# board.net
KiCad netlist of a schematic drawn in EAGLE
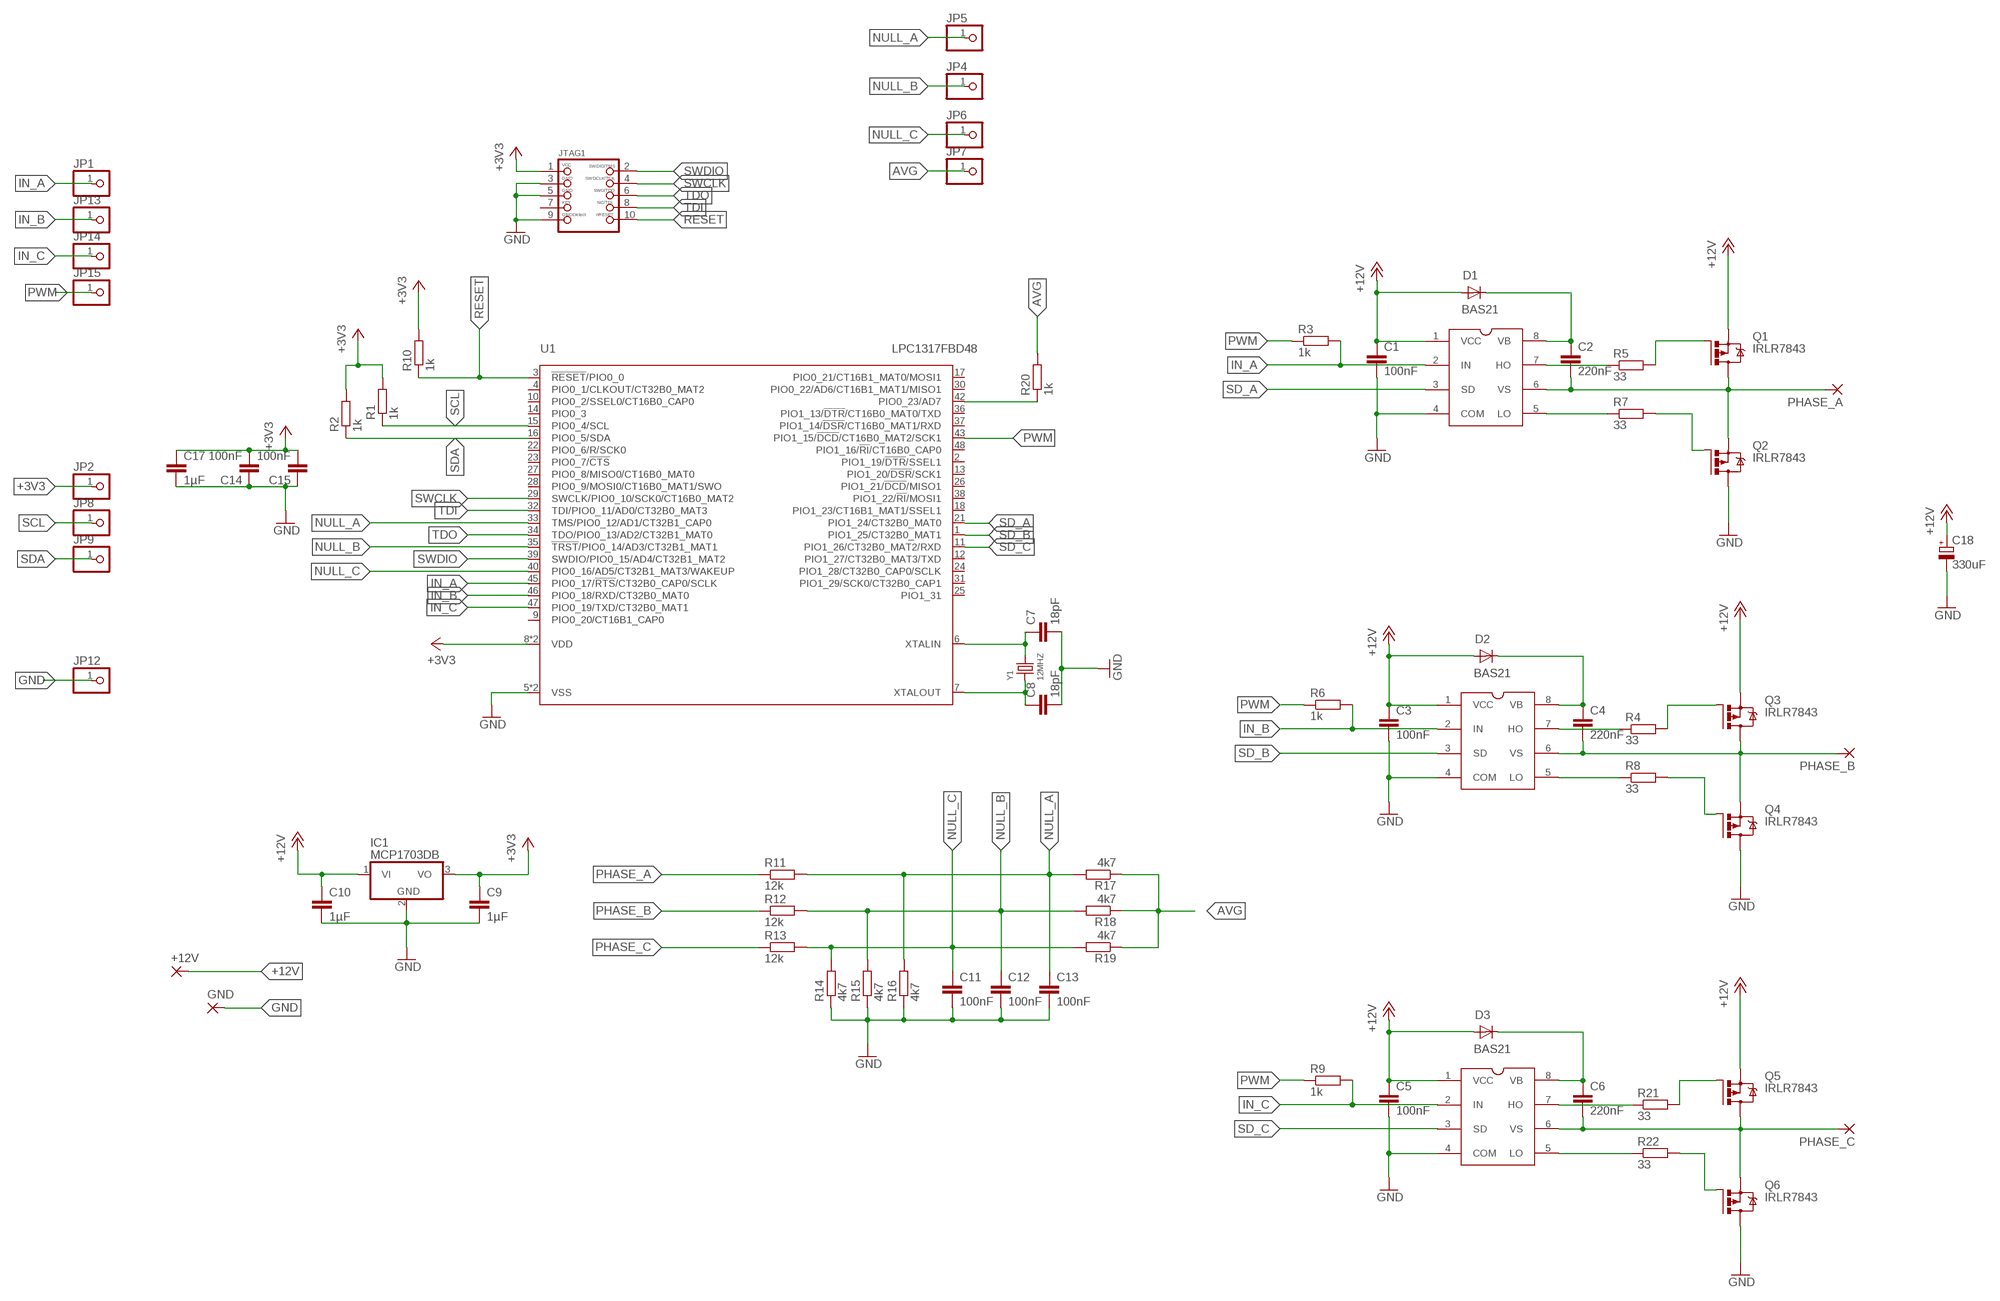
[diagram p0: schematic, sheet 1]

(export (version "E")
  (design (tool "Eeschema 10.0.6"))
  (components
    (comp (ref "+12V")
      (value "SMD5")
      (footprint "eagle-import:SMD2,54-5,08")
      (libsource (lib "eagle-import") (part "SMD5"))
    )
    (comp (ref "C1")
      (value "100nF")
      (footprint "eagle-import:C0603")
      (libsource (lib "eagle-import") (part "C-EUC0603"))
    )
    (comp (ref "C2")
      (value "220nF")
      (footprint "eagle-import:C0603")
      (libsource (lib "eagle-import") (part "C-EUC0603"))
    )
    (comp (ref "C3")
      (value "100nF")
      (footprint "eagle-import:C0603")
      (libsource (lib "eagle-import") (part "C-EUC0603"))
    )
    (comp (ref "C4")
      (value "220nF")
      (footprint "eagle-import:C0603")
      (libsource (lib "eagle-import") (part "C-EUC0603"))
    )
    (comp (ref "C5")
      (value "100nF")
      (footprint "eagle-import:C0603")
      (libsource (lib "eagle-import") (part "C-EUC0603"))
    )
    (comp (ref "C6")
      (value "220nF")
      (footprint "eagle-import:C0603")
      (libsource (lib "eagle-import") (part "C-EUC0603"))
    )
    (comp (ref "C7")
      (value "18pF")
      (footprint "eagle-import:C0603")
      (libsource (lib "eagle-import") (part "C-EUC0603"))
    )
    (comp (ref "C8")
      (value "18pF")
      (footprint "eagle-import:C0603")
      (libsource (lib "eagle-import") (part "C-EUC0603"))
    )
    (comp (ref "C9")
      (value "1µF")
      (footprint "eagle-import:C0603")
      (libsource (lib "eagle-import") (part "C-EUC0603"))
    )
    (comp (ref "C10")
      (value "1µF")
      (footprint "eagle-import:C0603")
      (libsource (lib "eagle-import") (part "C-EUC0603"))
    )
    (comp (ref "C11")
      (value "100nF")
      (footprint "eagle-import:C0603")
      (libsource (lib "eagle-import") (part "C-EUC0603"))
    )
    (comp (ref "C12")
      (value "100nF")
      (footprint "eagle-import:C0603")
      (libsource (lib "eagle-import") (part "C-EUC0603"))
    )
    (comp (ref "C13")
      (value "100nF")
      (footprint "eagle-import:C0603")
      (libsource (lib "eagle-import") (part "C-EUC0603"))
    )
    (comp (ref "C14")
      (value "100nF")
      (footprint "eagle-import:C0603")
      (libsource (lib "eagle-import") (part "C-EUC0603"))
    )
    (comp (ref "C15")
      (value "100nF")
      (footprint "eagle-import:C0603")
      (libsource (lib "eagle-import") (part "C-EUC0603"))
    )
    (comp (ref "C17")
      (value "1µF")
      (footprint "eagle-import:C0603")
      (libsource (lib "eagle-import") (part "C-EUC0603"))
    )
    (comp (ref "C18")
      (value "330uF")
      (footprint "eagle-import:E5-10,5")
      (libsource (lib "eagle-import") (part "CPOL-EUE5-10.5"))
    )
    (comp (ref "D1")
      (value "BAS21")
      (footprint "eagle-import:SOT23")
      (libsource (lib "eagle-import") (part "BAS21"))
    )
    (comp (ref "D2")
      (value "BAS21")
      (footprint "eagle-import:SOT23")
      (libsource (lib "eagle-import") (part "BAS21"))
    )
    (comp (ref "D3")
      (value "BAS21")
      (footprint "eagle-import:SOT23")
      (libsource (lib "eagle-import") (part "BAS21"))
    )
    (comp (ref "GND")
      (value "SMD5")
      (footprint "eagle-import:SMD2,54-5,08")
      (libsource (lib "eagle-import") (part "SMD5"))
    )
    (comp (ref "IC1")
      (value "MCP1703DB")
      (footprint "eagle-import:SOT223")
      (libsource (lib "eagle-import") (part "MCP1703DB"))
    )
    (comp (ref "JP1")
      (value "PINHD-1X1")
      (footprint "eagle-import:1X01")
      (libsource (lib "eagle-import") (part "PINHD-1X1"))
    )
    (comp (ref "JP2")
      (value "PINHD-1X1")
      (footprint "eagle-import:1X01")
      (libsource (lib "eagle-import") (part "PINHD-1X1"))
    )
    (comp (ref "JP4")
      (value "PINHD-1X1")
      (footprint "eagle-import:1X01")
      (libsource (lib "eagle-import") (part "PINHD-1X1"))
    )
    (comp (ref "JP5")
      (value "PINHD-1X1")
      (footprint "eagle-import:1X01")
      (libsource (lib "eagle-import") (part "PINHD-1X1"))
    )
    (comp (ref "JP6")
      (value "PINHD-1X1")
      (footprint "eagle-import:1X01")
      (libsource (lib "eagle-import") (part "PINHD-1X1"))
    )
    (comp (ref "JP7")
      (value "PINHD-1X1")
      (footprint "eagle-import:1X01")
      (libsource (lib "eagle-import") (part "PINHD-1X1"))
    )
    (comp (ref "JP8")
      (value "PINHD-1X1")
      (footprint "eagle-import:1X01")
      (libsource (lib "eagle-import") (part "PINHD-1X1"))
    )
    (comp (ref "JP9")
      (value "PINHD-1X1")
      (footprint "eagle-import:1X01")
      (libsource (lib "eagle-import") (part "PINHD-1X1"))
    )
    (comp (ref "JP12")
      (value "PINHD-1X1")
      (footprint "eagle-import:1X01")
      (libsource (lib "eagle-import") (part "PINHD-1X1"))
    )
    (comp (ref "JP13")
      (value "PINHD-1X1")
      (footprint "eagle-import:1X01")
      (libsource (lib "eagle-import") (part "PINHD-1X1"))
    )
    (comp (ref "JP14")
      (value "PINHD-1X1")
      (footprint "eagle-import:1X01")
      (libsource (lib "eagle-import") (part "PINHD-1X1"))
    )
    (comp (ref "JP15")
      (value "PINHD-1X1")
      (footprint "eagle-import:1X01")
      (libsource (lib "eagle-import") (part "PINHD-1X1"))
    )
    (comp (ref "JTAG1")
      (value "JTAG-CORTEXM3")
      (footprint "eagle-import:2X05_1.27MM_SMT")
      (libsource (lib "eagle-import") (part "JTAG-CORTEXM3"))
    )
    (comp (ref "PHASE_A")
      (value "SMD5")
      (footprint "eagle-import:SMD2,54-5,08")
      (libsource (lib "eagle-import") (part "SMD5"))
    )
    (comp (ref "PHASE_B")
      (value "SMD5")
      (footprint "eagle-import:SMD2,54-5,08")
      (libsource (lib "eagle-import") (part "SMD5"))
    )
    (comp (ref "PHASE_C")
      (value "SMD5")
      (footprint "eagle-import:SMD2,54-5,08")
      (libsource (lib "eagle-import") (part "SMD5"))
    )
    (comp (ref "Q1")
      (value "IRLR7843")
      (footprint "eagle-import:D-PAK_TO252AA")
      (libsource (lib "eagle-import") (part "IRF?5305R"))
    )
    (comp (ref "Q2")
      (value "IRLR7843")
      (footprint "eagle-import:D-PAK_TO252AA")
      (libsource (lib "eagle-import") (part "IRF?5305R"))
    )
    (comp (ref "Q3")
      (value "IRLR7843")
      (footprint "eagle-import:D-PAK_TO252AA")
      (libsource (lib "eagle-import") (part "IRF?5305R"))
    )
    (comp (ref "Q4")
      (value "IRLR7843")
      (footprint "eagle-import:D-PAK_TO252AA")
      (libsource (lib "eagle-import") (part "IRF?5305R"))
    )
    (comp (ref "Q5")
      (value "IRLR7843")
      (footprint "eagle-import:D-PAK_TO252AA")
      (libsource (lib "eagle-import") (part "IRF?5305R"))
    )
    (comp (ref "Q6")
      (value "IRLR7843")
      (footprint "eagle-import:D-PAK_TO252AA")
      (libsource (lib "eagle-import") (part "IRF?5305R"))
    )
    (comp (ref "R1")
      (value "1k")
      (footprint "eagle-import:R0603")
      (libsource (lib "eagle-import") (part "R-EU_R0603"))
    )
    (comp (ref "R2")
      (value "1k")
      (footprint "eagle-import:R0603")
      (libsource (lib "eagle-import") (part "R-EU_R0603"))
    )
    (comp (ref "R3")
      (value "1k")
      (footprint "eagle-import:R0603")
      (libsource (lib "eagle-import") (part "R-EU_R0603"))
    )
    (comp (ref "R4")
      (value "33")
      (footprint "eagle-import:R0603")
      (libsource (lib "eagle-import") (part "R-EU_R0603"))
    )
    (comp (ref "R5")
      (value "33")
      (footprint "eagle-import:R0603")
      (libsource (lib "eagle-import") (part "R-EU_R0603"))
    )
    (comp (ref "R6")
      (value "1k")
      (footprint "eagle-import:R0603")
      (libsource (lib "eagle-import") (part "R-EU_R0603"))
    )
    (comp (ref "R7")
      (value "33")
      (footprint "eagle-import:R0603")
      (libsource (lib "eagle-import") (part "R-EU_R0603"))
    )
    (comp (ref "R8")
      (value "33")
      (footprint "eagle-import:R0603")
      (libsource (lib "eagle-import") (part "R-EU_R0603"))
    )
    (comp (ref "R9")
      (value "1k")
      (footprint "eagle-import:R0603")
      (libsource (lib "eagle-import") (part "R-EU_R0603"))
    )
    (comp (ref "R10")
      (value "1k")
      (footprint "eagle-import:R0603")
      (libsource (lib "eagle-import") (part "R-EU_R0603"))
    )
    (comp (ref "R11")
      (value "12k")
      (footprint "eagle-import:R0603")
      (libsource (lib "eagle-import") (part "R-EU_R0603"))
    )
    (comp (ref "R12")
      (value "12k")
      (footprint "eagle-import:R0603")
      (libsource (lib "eagle-import") (part "R-EU_R0603"))
    )
    (comp (ref "R13")
      (value "12k")
      (footprint "eagle-import:R0603")
      (libsource (lib "eagle-import") (part "R-EU_R0603"))
    )
    (comp (ref "R14")
      (value "4k7")
      (footprint "eagle-import:R0603")
      (libsource (lib "eagle-import") (part "R-EU_R0603"))
    )
    (comp (ref "R15")
      (value "4k7")
      (footprint "eagle-import:R0603")
      (libsource (lib "eagle-import") (part "R-EU_R0603"))
    )
    (comp (ref "R16")
      (value "4k7")
      (footprint "eagle-import:R0603")
      (libsource (lib "eagle-import") (part "R-EU_R0603"))
    )
    (comp (ref "R17")
      (value "4k7")
      (footprint "eagle-import:R0603")
      (libsource (lib "eagle-import") (part "R-EU_R0603"))
    )
    (comp (ref "R18")
      (value "4k7")
      (footprint "eagle-import:R0603")
      (libsource (lib "eagle-import") (part "R-EU_R0603"))
    )
    (comp (ref "R19")
      (value "4k7")
      (footprint "eagle-import:R0603")
      (libsource (lib "eagle-import") (part "R-EU_R0603"))
    )
    (comp (ref "R20")
      (value "1k")
      (footprint "eagle-import:R0603")
      (libsource (lib "eagle-import") (part "R-EU_R0603"))
    )
    (comp (ref "R21")
      (value "33")
      (footprint "eagle-import:R0603")
      (libsource (lib "eagle-import") (part "R-EU_R0603"))
    )
    (comp (ref "R22")
      (value "33")
      (footprint "eagle-import:R0603")
      (libsource (lib "eagle-import") (part "R-EU_R0603"))
    )
    (comp (ref "U$1")
      (value "IR2104S")
      (footprint "eagle-import:IR2104S")
      (libsource (lib "eagle-import") (part "IR2104S"))
    )
    (comp (ref "U$2")
      (value "IR2104S")
      (footprint "eagle-import:IR2104S")
      (libsource (lib "eagle-import") (part "IR2104S"))
    )
    (comp (ref "U$3")
      (value "IR2104S")
      (footprint "eagle-import:IR2104S")
      (libsource (lib "eagle-import") (part "IR2104S"))
    )
    (comp (ref "U1")
      (value "LPC1317FBD48")
      (footprint "eagle-import:SOT313-2")
      (libsource (lib "eagle-import") (part "LPC1317FBD48"))
    )
    (comp (ref "Y1")
      (value "12MHZ")
      (footprint "eagle-import:CRYSTAL_3.2X2.5")
      (libsource (lib "eagle-import") (part "CRYSTALTHIN"))
    )
  )
  (nets
    (net (code "1") (name "+3V3") (class "Default")
      (node (ref "C14") (pin "2") (pinfunction "2_2") (pintype "passive"))
      (node (ref "C15") (pin "2") (pinfunction "2_2") (pintype "passive"))
      (node (ref "C17") (pin "1") (pinfunction "1_1") (pintype "passive"))
      (node (ref "C9") (pin "1") (pinfunction "1_1") (pintype "passive"))
      (node (ref "IC1") (pin "3") (pinfunction "VO_3") (pintype "passive"))
      (node (ref "JP2") (pin "1") (pinfunction "1_1") (pintype "passive"))
      (node (ref "JTAG1") (pin "1") (pinfunction "1_1") (pintype "passive"))
      (node (ref "R1") (pin "2") (pinfunction "2_2") (pintype "passive"))
      (node (ref "R10") (pin "2") (pinfunction "2_2") (pintype "passive"))
      (node (ref "R2") (pin "2") (pinfunction "2_2") (pintype "passive"))
      (node (ref "U1") (pin "44") (pinfunction "VDD_44") (pintype "power_in"))
      (node (ref "U1") (pin "8") (pinfunction "VDD_8") (pintype "power_in"))
    )
    (net (code "2") (name "+12V") (class "Default")
      (node (ref "+12V") (pin "1") (pinfunction "P_1") (pintype "passive"))
      (node (ref "C1") (pin "1") (pinfunction "1_1") (pintype "passive"))
      (node (ref "C10") (pin "1") (pinfunction "1_1") (pintype "passive"))
      (node (ref "C18") (pin "+") (pinfunction "+_+") (pintype "passive"))
      (node (ref "C3") (pin "1") (pinfunction "1_1") (pintype "passive"))
      (node (ref "C5") (pin "1") (pinfunction "1_1") (pintype "passive"))
      (node (ref "D1") (pin "1") (pinfunction "A_1") (pintype "passive"))
      (node (ref "D2") (pin "1") (pinfunction "A_1") (pintype "passive"))
      (node (ref "D3") (pin "1") (pinfunction "A_1") (pintype "passive"))
      (node (ref "IC1") (pin "1") (pinfunction "VI_1") (pintype "input"))
      (node (ref "Q1") (pin "3") (pinfunction "S_3") (pintype "passive"))
      (node (ref "Q3") (pin "3") (pinfunction "S_3") (pintype "passive"))
      (node (ref "Q5") (pin "3") (pinfunction "S_3") (pintype "passive"))
      (node (ref "U$1") (pin "1") (pinfunction "VCC_1") (pintype "power_in"))
      (node (ref "U$2") (pin "1") (pinfunction "VCC_1") (pintype "power_in"))
      (node (ref "U$3") (pin "1") (pinfunction "VCC_1") (pintype "power_in"))
    )
    (net (code "3") (name "AVG") (class "Default")
      (node (ref "JP7") (pin "1") (pinfunction "1_1") (pintype "passive"))
      (node (ref "R17") (pin "1") (pinfunction "1_1") (pintype "passive"))
      (node (ref "R18") (pin "1") (pinfunction "1_1") (pintype "passive"))
      (node (ref "R19") (pin "1") (pinfunction "1_1") (pintype "passive"))
      (node (ref "R20") (pin "2") (pinfunction "2_2") (pintype "passive"))
    )
    (net (code "4") (name "GND") (class "Default")
      (node (ref "C1") (pin "2") (pinfunction "2_2") (pintype "passive"))
      (node (ref "C10") (pin "2") (pinfunction "2_2") (pintype "passive"))
      (node (ref "C11") (pin "2") (pinfunction "2_2") (pintype "passive"))
      (node (ref "C12") (pin "2") (pinfunction "2_2") (pintype "passive"))
      (node (ref "C13") (pin "2") (pinfunction "2_2") (pintype "passive"))
      (node (ref "C14") (pin "1") (pinfunction "1_1") (pintype "passive"))
      (node (ref "C15") (pin "1") (pinfunction "1_1") (pintype "passive"))
      (node (ref "C17") (pin "2") (pinfunction "2_2") (pintype "passive"))
      (node (ref "C18") (pin "-") (pinfunction "-_-") (pintype "passive"))
      (node (ref "C3") (pin "2") (pinfunction "2_2") (pintype "passive"))
      (node (ref "C5") (pin "2") (pinfunction "2_2") (pintype "passive"))
      (node (ref "C7") (pin "2") (pinfunction "2_2") (pintype "passive"))
      (node (ref "C8") (pin "2") (pinfunction "2_2") (pintype "passive"))
      (node (ref "C9") (pin "2") (pinfunction "2_2") (pintype "passive"))
      (node (ref "GND") (pin "1") (pinfunction "P_1") (pintype "passive"))
      (node (ref "IC1") (pin "2") (pinfunction "GND_2") (pintype "passive"))
      (node (ref "JP12") (pin "1") (pinfunction "1_1") (pintype "passive"))
      (node (ref "JTAG1") (pin "3") (pinfunction "3_3") (pintype "passive"))
      (node (ref "JTAG1") (pin "5") (pinfunction "5_5") (pintype "passive"))
      (node (ref "JTAG1") (pin "9") (pinfunction "9_9") (pintype "passive"))
      (node (ref "Q2") (pin "4") (pinfunction "D_4") (pintype "passive"))
      (node (ref "Q4") (pin "4") (pinfunction "D_4") (pintype "passive"))
      (node (ref "Q6") (pin "4") (pinfunction "D_4") (pintype "passive"))
      (node (ref "R14") (pin "1") (pinfunction "1_1") (pintype "passive"))
      (node (ref "R15") (pin "1") (pinfunction "1_1") (pintype "passive"))
      (node (ref "R16") (pin "1") (pinfunction "1_1") (pintype "passive"))
      (node (ref "U$1") (pin "4") (pinfunction "COM_4") (pintype "bidirectional"))
      (node (ref "U$2") (pin "4") (pinfunction "COM_4") (pintype "bidirectional"))
      (node (ref "U$3") (pin "4") (pinfunction "COM_4") (pintype "bidirectional"))
      (node (ref "U1") (pin "41") (pinfunction "VSS_41") (pintype "power_in"))
      (node (ref "U1") (pin "5") (pinfunction "VSS_5") (pintype "power_in"))
    )
    (net (code "5") (name "IN_A") (class "Default")
      (node (ref "JP1") (pin "1") (pinfunction "1_1") (pintype "passive"))
      (node (ref "R3") (pin "2") (pinfunction "2_2") (pintype "passive"))
      (node (ref "U$1") (pin "2") (pinfunction "IN_2") (pintype "bidirectional"))
      (node (ref "U1") (pin "45") (pinfunction "PIO0_17/~{RTS}/CT32B0_CAP0/SCLK_45") (pintype "bidirectional"))
    )
    (net (code "6") (name "IN_B") (class "Default")
      (node (ref "JP13") (pin "1") (pinfunction "1_1") (pintype "passive"))
      (node (ref "R6") (pin "2") (pinfunction "2_2") (pintype "passive"))
      (node (ref "U$2") (pin "2") (pinfunction "IN_2") (pintype "bidirectional"))
      (node (ref "U1") (pin "46") (pinfunction "PIO0_18/RXD/CT32B0_MAT0_46") (pintype "bidirectional"))
    )
    (net (code "7") (name "IN_C") (class "Default")
      (node (ref "JP14") (pin "1") (pinfunction "1_1") (pintype "passive"))
      (node (ref "R9") (pin "2") (pinfunction "2_2") (pintype "passive"))
      (node (ref "U$3") (pin "2") (pinfunction "IN_2") (pintype "bidirectional"))
      (node (ref "U1") (pin "47") (pinfunction "PIO0_19/TXD/CT32B0_MAT1_47") (pintype "bidirectional"))
    )
    (net (code "8") (name "NULL_A") (class "Default")
      (node (ref "C13") (pin "1") (pinfunction "1_1") (pintype "passive"))
      (node (ref "JP5") (pin "1") (pinfunction "1_1") (pintype "passive"))
      (node (ref "R11") (pin "2") (pinfunction "2_2") (pintype "passive"))
      (node (ref "R16") (pin "2") (pinfunction "2_2") (pintype "passive"))
      (node (ref "R17") (pin "2") (pinfunction "2_2") (pintype "passive"))
      (node (ref "U1") (pin "33") (pinfunction "TMS/PIO0_12/AD1/CT32B1_CAP0_33") (pintype "bidirectional"))
    )
    (net (code "9") (name "NULL_B") (class "Default")
      (node (ref "C12") (pin "1") (pinfunction "1_1") (pintype "passive"))
      (node (ref "JP4") (pin "1") (pinfunction "1_1") (pintype "passive"))
      (node (ref "R12") (pin "2") (pinfunction "2_2") (pintype "passive"))
      (node (ref "R15") (pin "2") (pinfunction "2_2") (pintype "passive"))
      (node (ref "R18") (pin "2") (pinfunction "2_2") (pintype "passive"))
      (node (ref "U1") (pin "35") (pinfunction "~{TRST}/PIO0_14/AD3/CT32B1_MAT1_35") (pintype "bidirectional"))
    )
    (net (code "10") (name "NULL_C") (class "Default")
      (node (ref "C11") (pin "1") (pinfunction "1_1") (pintype "passive"))
      (node (ref "JP6") (pin "1") (pinfunction "1_1") (pintype "passive"))
      (node (ref "R13") (pin "2") (pinfunction "2_2") (pintype "passive"))
      (node (ref "R14") (pin "2") (pinfunction "2_2") (pintype "passive"))
      (node (ref "R19") (pin "2") (pinfunction "2_2") (pintype "passive"))
      (node (ref "U1") (pin "40") (pinfunction "PIO0_16/AD5/CT32B1_MAT3/WAKEUP_40") (pintype "bidirectional"))
    )
    (net (code "11") (name "Net-(D1-K)") (class "Default")
      (node (ref "C2") (pin "1") (pinfunction "1_1") (pintype "passive"))
      (node (ref "D1") (pin "3") (pinfunction "K_3") (pintype "passive"))
      (node (ref "U$1") (pin "8") (pinfunction "VB_8") (pintype "power_in"))
    )
    (net (code "12") (name "Net-(D2-K)") (class "Default")
      (node (ref "C4") (pin "1") (pinfunction "1_1") (pintype "passive"))
      (node (ref "D2") (pin "3") (pinfunction "K_3") (pintype "passive"))
      (node (ref "U$2") (pin "8") (pinfunction "VB_8") (pintype "power_in"))
    )
    (net (code "13") (name "Net-(D3-K)") (class "Default")
      (node (ref "C6") (pin "1") (pinfunction "1_1") (pintype "passive"))
      (node (ref "D3") (pin "3") (pinfunction "K_3") (pintype "passive"))
      (node (ref "U$3") (pin "8") (pinfunction "VB_8") (pintype "power_in"))
    )
    (net (code "14") (name "Net-(Q1-G)") (class "Default")
      (node (ref "Q1") (pin "1") (pinfunction "G_1") (pintype "passive"))
      (node (ref "R5") (pin "2") (pinfunction "2_2") (pintype "passive"))
    )
    (net (code "15") (name "Net-(Q2-G)") (class "Default")
      (node (ref "Q2") (pin "1") (pinfunction "G_1") (pintype "passive"))
      (node (ref "R7") (pin "2") (pinfunction "2_2") (pintype "passive"))
    )
    (net (code "16") (name "Net-(Q3-G)") (class "Default")
      (node (ref "Q3") (pin "1") (pinfunction "G_1") (pintype "passive"))
      (node (ref "R4") (pin "2") (pinfunction "2_2") (pintype "passive"))
    )
    (net (code "17") (name "Net-(Q4-G)") (class "Default")
      (node (ref "Q4") (pin "1") (pinfunction "G_1") (pintype "passive"))
      (node (ref "R8") (pin "2") (pinfunction "2_2") (pintype "passive"))
    )
    (net (code "18") (name "Net-(Q5-G)") (class "Default")
      (node (ref "Q5") (pin "1") (pinfunction "G_1") (pintype "passive"))
      (node (ref "R21") (pin "2") (pinfunction "2_2") (pintype "passive"))
    )
    (net (code "19") (name "Net-(Q6-G)") (class "Default")
      (node (ref "Q6") (pin "1") (pinfunction "G_1") (pintype "passive"))
      (node (ref "R22") (pin "2") (pinfunction "2_2") (pintype "passive"))
    )
    (net (code "20") (name "Net-(U$1-HO)") (class "Default")
      (node (ref "R5") (pin "1") (pinfunction "1_1") (pintype "passive"))
      (node (ref "U$1") (pin "7") (pinfunction "HO_7") (pintype "bidirectional"))
    )
    (net (code "21") (name "Net-(U$1-LO)") (class "Default")
      (node (ref "R7") (pin "1") (pinfunction "1_1") (pintype "passive"))
      (node (ref "U$1") (pin "5") (pinfunction "LO_5") (pintype "bidirectional"))
    )
    (net (code "22") (name "Net-(U$2-HO)") (class "Default")
      (node (ref "R4") (pin "1") (pinfunction "1_1") (pintype "passive"))
      (node (ref "U$2") (pin "7") (pinfunction "HO_7") (pintype "bidirectional"))
    )
    (net (code "23") (name "Net-(U$2-LO)") (class "Default")
      (node (ref "R8") (pin "1") (pinfunction "1_1") (pintype "passive"))
      (node (ref "U$2") (pin "5") (pinfunction "LO_5") (pintype "bidirectional"))
    )
    (net (code "24") (name "Net-(U$3-HO)") (class "Default")
      (node (ref "R21") (pin "1") (pinfunction "1_1") (pintype "passive"))
      (node (ref "U$3") (pin "7") (pinfunction "HO_7") (pintype "bidirectional"))
    )
    (net (code "25") (name "Net-(U$3-LO)") (class "Default")
      (node (ref "R22") (pin "1") (pinfunction "1_1") (pintype "passive"))
      (node (ref "U$3") (pin "5") (pinfunction "LO_5") (pintype "bidirectional"))
    )
    (net (code "26") (name "Net-(U1-PIO0_23{slash}AD7)") (class "Default")
      (node (ref "R20") (pin "1") (pinfunction "1_1") (pintype "passive"))
      (node (ref "U1") (pin "42") (pinfunction "PIO0_23/AD7_42") (pintype "bidirectional"))
    )
    (net (code "27") (name "Net-(U1-XTALIN)") (class "Default")
      (node (ref "C7") (pin "1") (pinfunction "1_1") (pintype "passive"))
      (node (ref "U1") (pin "6") (pinfunction "XTALIN_6") (pintype "input"))
      (node (ref "Y1") (pin "2") (pinfunction "2_2") (pintype "passive"))
    )
    (net (code "28") (name "Net-(U1-XTALOUT)") (class "Default")
      (node (ref "C8") (pin "1") (pinfunction "1_1") (pintype "passive"))
      (node (ref "U1") (pin "7") (pinfunction "XTALOUT_7") (pintype "output"))
      (node (ref "Y1") (pin "1") (pinfunction "1_1") (pintype "passive"))
    )
    (net (code "29") (name "PHASE_A") (class "Default")
      (node (ref "C2") (pin "2") (pinfunction "2_2") (pintype "passive"))
      (node (ref "PHASE_A") (pin "1") (pinfunction "P_1") (pintype "passive"))
      (node (ref "Q1") (pin "4") (pinfunction "D_4") (pintype "passive"))
      (node (ref "Q2") (pin "3") (pinfunction "S_3") (pintype "passive"))
      (node (ref "R11") (pin "1") (pinfunction "1_1") (pintype "passive"))
      (node (ref "U$1") (pin "6") (pinfunction "VS_6") (pintype "power_in"))
    )
    (net (code "30") (name "PHASE_B") (class "Default")
      (node (ref "C4") (pin "2") (pinfunction "2_2") (pintype "passive"))
      (node (ref "PHASE_B") (pin "1") (pinfunction "P_1") (pintype "passive"))
      (node (ref "Q3") (pin "4") (pinfunction "D_4") (pintype "passive"))
      (node (ref "Q4") (pin "3") (pinfunction "S_3") (pintype "passive"))
      (node (ref "R12") (pin "1") (pinfunction "1_1") (pintype "passive"))
      (node (ref "U$2") (pin "6") (pinfunction "VS_6") (pintype "power_in"))
    )
    (net (code "31") (name "PHASE_C") (class "Default")
      (node (ref "C6") (pin "2") (pinfunction "2_2") (pintype "passive"))
      (node (ref "PHASE_C") (pin "1") (pinfunction "P_1") (pintype "passive"))
      (node (ref "Q5") (pin "4") (pinfunction "D_4") (pintype "passive"))
      (node (ref "Q6") (pin "3") (pinfunction "S_3") (pintype "passive"))
      (node (ref "R13") (pin "1") (pinfunction "1_1") (pintype "passive"))
      (node (ref "U$3") (pin "6") (pinfunction "VS_6") (pintype "power_in"))
    )
    (net (code "32") (name "PWM") (class "Default")
      (node (ref "JP15") (pin "1") (pinfunction "1_1") (pintype "passive"))
      (node (ref "R3") (pin "1") (pinfunction "1_1") (pintype "passive"))
      (node (ref "R6") (pin "1") (pinfunction "1_1") (pintype "passive"))
      (node (ref "R9") (pin "1") (pinfunction "1_1") (pintype "passive"))
      (node (ref "U1") (pin "43") (pinfunction "PIO1_15/~{DCD}/CT16B0_MAT2/SCK1_43") (pintype "bidirectional"))
    )
    (net (code "33") (name "RESET") (class "Default")
      (node (ref "JTAG1") (pin "10") (pinfunction "10_10") (pintype "passive"))
      (node (ref "R10") (pin "1") (pinfunction "1_1") (pintype "passive"))
      (node (ref "U1") (pin "3") (pinfunction "~{RESET}/PIO0_0_3") (pintype "bidirectional"))
    )
    (net (code "34") (name "SCL") (class "Default")
      (node (ref "JP8") (pin "1") (pinfunction "1_1") (pintype "passive"))
      (node (ref "R1") (pin "1") (pinfunction "1_1") (pintype "passive"))
      (node (ref "U1") (pin "15") (pinfunction "PIO0_4/SCL_15") (pintype "bidirectional"))
    )
    (net (code "35") (name "SDA") (class "Default")
      (node (ref "JP9") (pin "1") (pinfunction "1_1") (pintype "passive"))
      (node (ref "R2") (pin "1") (pinfunction "1_1") (pintype "passive"))
      (node (ref "U1") (pin "16") (pinfunction "PIO0_5/SDA_16") (pintype "bidirectional"))
    )
    (net (code "36") (name "SD_A") (class "Default")
      (node (ref "U$1") (pin "3") (pinfunction "SD_3") (pintype "bidirectional"))
      (node (ref "U1") (pin "21") (pinfunction "PIO1_24/CT32B0_MAT0_21") (pintype "bidirectional"))
    )
    (net (code "37") (name "SD_B") (class "Default")
      (node (ref "U$2") (pin "3") (pinfunction "SD_3") (pintype "bidirectional"))
      (node (ref "U1") (pin "1") (pinfunction "PIO1_25/CT32B0_MAT1_1") (pintype "bidirectional"))
    )
    (net (code "38") (name "SD_C") (class "Default")
      (node (ref "U$3") (pin "3") (pinfunction "SD_3") (pintype "bidirectional"))
      (node (ref "U1") (pin "11") (pinfunction "PIO1_26/CT32B0_MAT2/RXD_11") (pintype "bidirectional"))
    )
    (net (code "39") (name "SWCLK") (class "Default")
      (node (ref "JTAG1") (pin "4") (pinfunction "4_4") (pintype "passive"))
      (node (ref "U1") (pin "29") (pinfunction "SWCLK/PIO0_10/SCK0/CT16B0_MAT2_29") (pintype "bidirectional"))
    )
    (net (code "40") (name "SWDIO") (class "Default")
      (node (ref "JTAG1") (pin "2") (pinfunction "2_2") (pintype "passive"))
      (node (ref "U1") (pin "39") (pinfunction "SWDIO/PIO0_15/AD4/CT32B1_MAT2_39") (pintype "bidirectional"))
    )
    (net (code "41") (name "TDI") (class "Default")
      (node (ref "JTAG1") (pin "8") (pinfunction "8_8") (pintype "passive"))
      (node (ref "U1") (pin "32") (pinfunction "TDI/PIO0_11/AD0/CT32B0_MAT3_32") (pintype "bidirectional"))
    )
    (net (code "42") (name "TDO") (class "Default")
      (node (ref "JTAG1") (pin "6") (pinfunction "6_6") (pintype "passive"))
      (node (ref "U1") (pin "34") (pinfunction "TDO/PIO0_13/AD2/CT32B1_MAT0_34") (pintype "bidirectional"))
    )
    (net (code "43") (name "unconnected-(JTAG1-Pad7)") (class "Default")
      (node (ref "JTAG1") (pin "7") (pinfunction "7_7") (pintype "passive"))
    )
    (net (code "44") (name "unconnected-(U1-PIO0_1{slash}CLKOUT{slash}CT32B0_MAT2-Pad4)") (class "Default")
      (node (ref "U1") (pin "4") (pinfunction "PIO0_1/CLKOUT/CT32B0_MAT2_4") (pintype "bidirectional"))
    )
    (net (code "45") (name "unconnected-(U1-PIO0_2{slash}SSEL0{slash}CT16B0_CAP0-Pad10)") (class "Default")
      (node (ref "U1") (pin "10") (pinfunction "PIO0_2/SSEL0/CT16B0_CAP0_10") (pintype "bidirectional"))
    )
    (net (code "46") (name "unconnected-(U1-PIO0_3-Pad14)") (class "Default")
      (node (ref "U1") (pin "14") (pinfunction "PIO0_3_14") (pintype "bidirectional"))
    )
    (net (code "47") (name "unconnected-(U1-PIO0_6{slash}R{slash}SCK0-Pad22)") (class "Default")
      (node (ref "U1") (pin "22") (pinfunction "PIO0_6/R/SCK0_22") (pintype "bidirectional"))
    )
    (net (code "48") (name "unconnected-(U1-PIO0_7{slash}~{CTS}-Pad23)") (class "Default")
      (node (ref "U1") (pin "23") (pinfunction "PIO0_7/~{CTS}_23") (pintype "bidirectional"))
    )
    (net (code "49") (name "unconnected-(U1-PIO0_8{slash}MISO0{slash}CT16B0_MAT0-Pad27)") (class "Default")
      (node (ref "U1") (pin "27") (pinfunction "PIO0_8/MISO0/CT16B0_MAT0_27") (pintype "bidirectional"))
    )
    (net (code "50") (name "unconnected-(U1-PIO0_9{slash}MOSI0{slash}CT16B0_MAT1{slash}SWO-Pad28)") (class "Default")
      (node (ref "U1") (pin "28") (pinfunction "PIO0_9/MOSI0/CT16B0_MAT1/SWO_28") (pintype "bidirectional"))
    )
    (net (code "51") (name "unconnected-(U1-PIO0_20{slash}CT16B1_CAP0-Pad9)") (class "Default")
      (node (ref "U1") (pin "9") (pinfunction "PIO0_20/CT16B1_CAP0_9") (pintype "bidirectional"))
    )
    (net (code "52") (name "unconnected-(U1-PIO0_21{slash}CT16B1_MAT0{slash}MOSI1-Pad17)") (class "Default")
      (node (ref "U1") (pin "17") (pinfunction "PIO0_21/CT16B1_MAT0/MOSI1_17") (pintype "bidirectional"))
    )
    (net (code "53") (name "unconnected-(U1-PIO0_22{slash}AD6{slash}CT16B1_MAT1{slash}MISO1-Pad30)") (class "Default")
      (node (ref "U1") (pin "30") (pinfunction "PIO0_22/AD6/CT16B1_MAT1/MISO1_30") (pintype "bidirectional"))
    )
    (net (code "54") (name "unconnected-(U1-PIO1_13{slash}~{DTR}{slash}CT16B0_MAT0{slash}TXD-Pad36)") (class "Default")
      (node (ref "U1") (pin "36") (pinfunction "PIO1_13/~{DTR}/CT16B0_MAT0/TXD_36") (pintype "bidirectional"))
    )
    (net (code "55") (name "unconnected-(U1-PIO1_14{slash}~{DSR}{slash}CT16B0_MAT1{slash}RXD-Pad37)") (class "Default")
      (node (ref "U1") (pin "37") (pinfunction "PIO1_14/~{DSR}/CT16B0_MAT1/RXD_37") (pintype "bidirectional"))
    )
    (net (code "56") (name "unconnected-(U1-PIO1_16{slash}~{RI}{slash}CT16B0_CAP0-Pad48)") (class "Default")
      (node (ref "U1") (pin "48") (pinfunction "PIO1_16/~{RI}/CT16B0_CAP0_48") (pintype "bidirectional"))
    )
    (net (code "57") (name "unconnected-(U1-PIO1_19{slash}~{DTR}{slash}SSEL1-Pad2)") (class "Default")
      (node (ref "U1") (pin "2") (pinfunction "PIO1_19/~{DTR}/SSEL1_2") (pintype "bidirectional"))
    )
    (net (code "58") (name "unconnected-(U1-PIO1_20{slash}~{DSR}{slash}SCK1-Pad13)") (class "Default")
      (node (ref "U1") (pin "13") (pinfunction "PIO1_20/~{DSR}/SCK1_13") (pintype "bidirectional"))
    )
    (net (code "59") (name "unconnected-(U1-PIO1_21{slash}~{DCD}{slash}MISO1-Pad26)") (class "Default")
      (node (ref "U1") (pin "26") (pinfunction "PIO1_21/~{DCD}/MISO1_26") (pintype "bidirectional"))
    )
    (net (code "60") (name "unconnected-(U1-PIO1_22{slash}~{RI}{slash}MOSI1-Pad38)") (class "Default")
      (node (ref "U1") (pin "38") (pinfunction "PIO1_22/~{RI}/MOSI1_38") (pintype "bidirectional"))
    )
    (net (code "61") (name "unconnected-(U1-PIO1_23{slash}CT16B1_MAT1{slash}SSEL1-Pad18)") (class "Default")
      (node (ref "U1") (pin "18") (pinfunction "PIO1_23/CT16B1_MAT1/SSEL1_18") (pintype "bidirectional"))
    )
    (net (code "62") (name "unconnected-(U1-PIO1_27{slash}CT32B0_MAT3{slash}TXD-Pad12)") (class "Default")
      (node (ref "U1") (pin "12") (pinfunction "PIO1_27/CT32B0_MAT3/TXD_12") (pintype "bidirectional"))
    )
    (net (code "63") (name "unconnected-(U1-PIO1_28{slash}CT32B0_CAP0{slash}SCLK-Pad24)") (class "Default")
      (node (ref "U1") (pin "24") (pinfunction "PIO1_28/CT32B0_CAP0/SCLK_24") (pintype "bidirectional"))
    )
    (net (code "64") (name "unconnected-(U1-PIO1_29{slash}SCK0{slash}CT32B0_CAP1-Pad31)") (class "Default")
      (node (ref "U1") (pin "31") (pinfunction "PIO1_29/SCK0/CT32B0_CAP1_31") (pintype "bidirectional"))
    )
    (net (code "65") (name "unconnected-(U1-PIO1_31-Pad25)") (class "Default")
      (node (ref "U1") (pin "25") (pinfunction "PIO1_31_25") (pintype "bidirectional"))
    )
  )
)
